# SAMD21.net
KiCad netlist of a schematic drawn in EAGLE
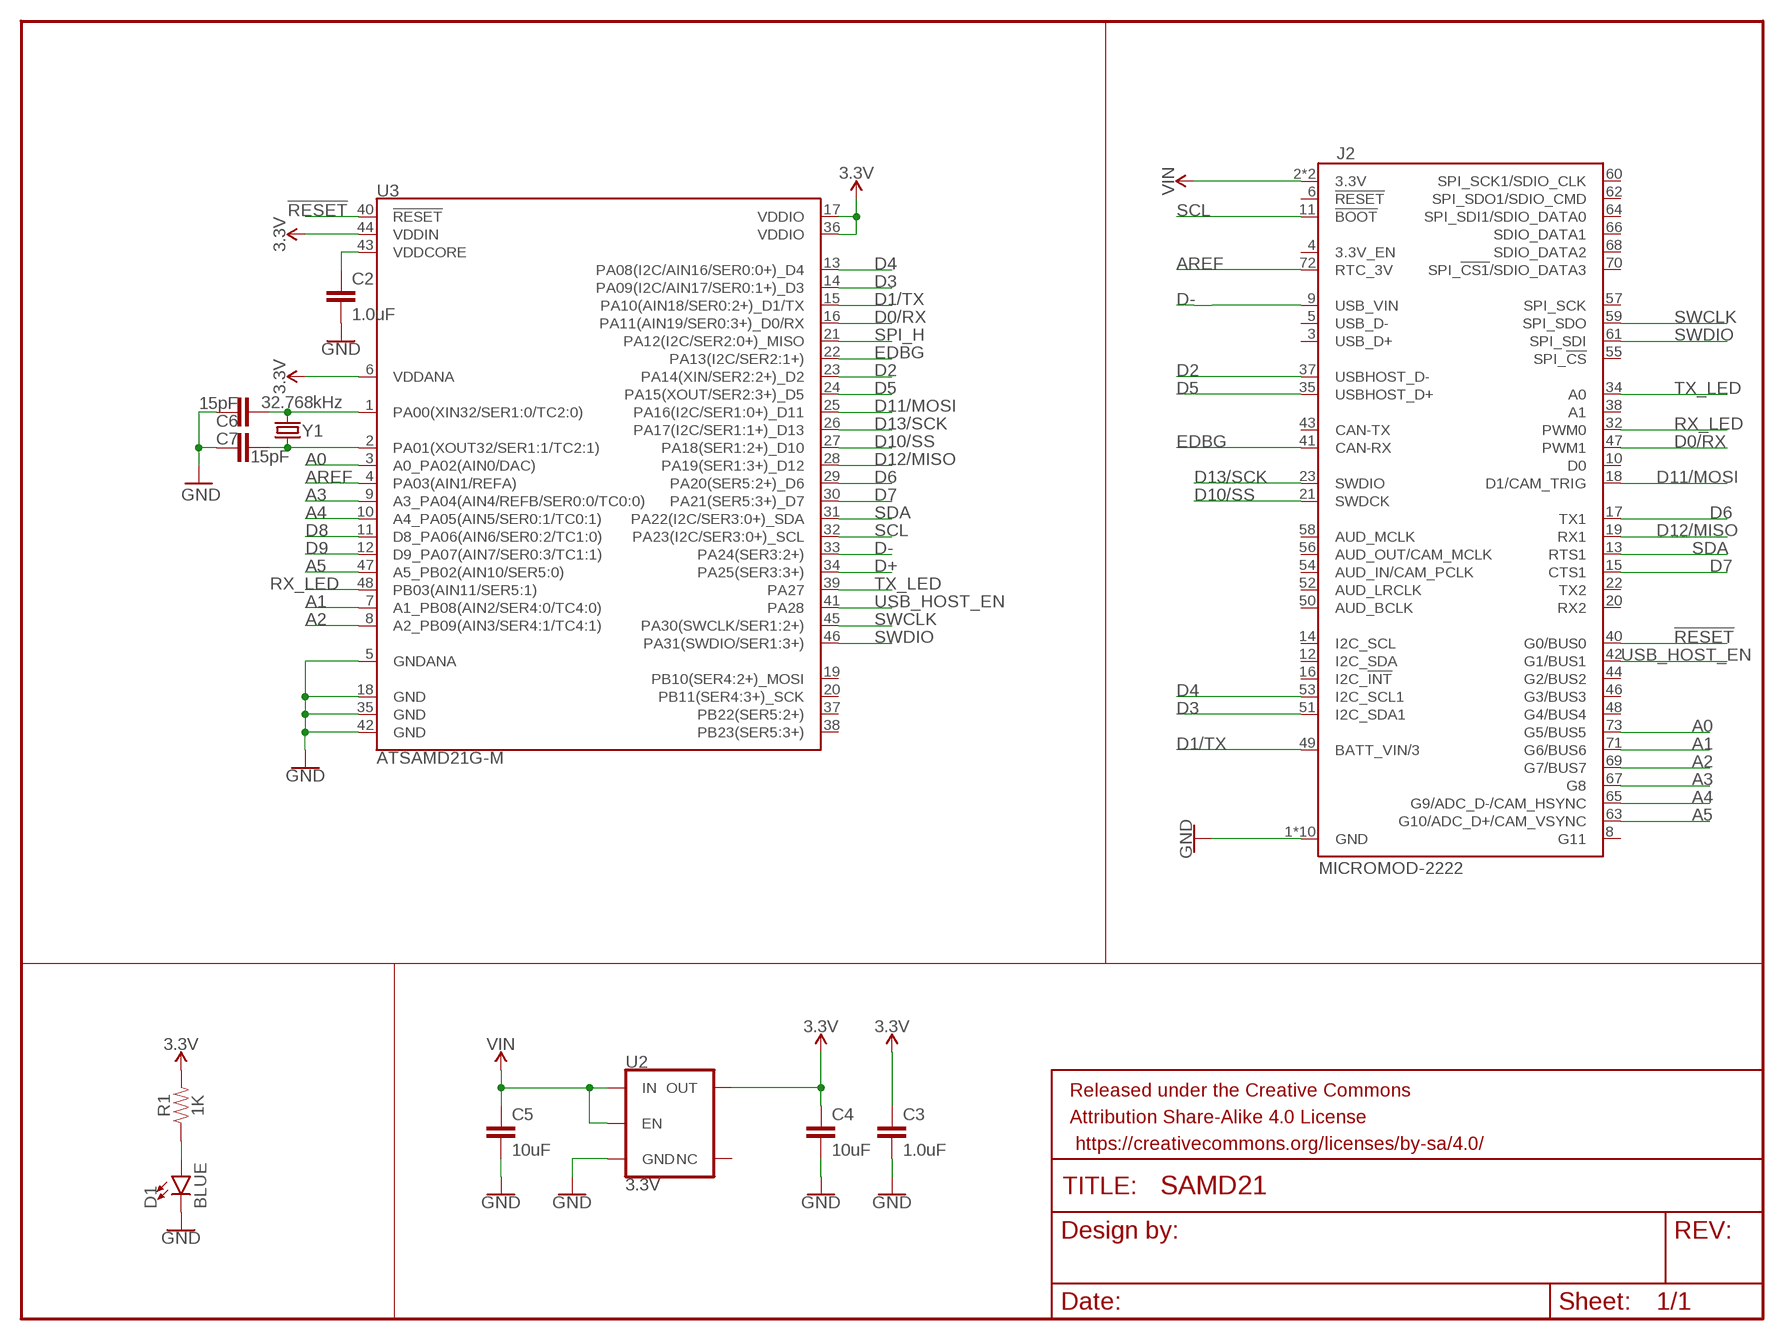
[diagram p0: schematic, sheet 1]

(export (version "E")
  (design (tool "Eeschema 10.0.6"))
  (components
    (comp (ref "C2")
      (value "1.0uF")
      (footprint "eagle-import:0603")
      (libsource (lib "eagle-import") (part "1.0UF-0603-16V-10%-X7R"))
    )
    (comp (ref "C3")
      (value "1.0uF")
      (footprint "eagle-import:0603")
      (libsource (lib "eagle-import") (part "1.0UF-0603-16V-10%-X7R"))
    )
    (comp (ref "C4")
      (value "10uF")
      (footprint "eagle-import:0603")
      (libsource (lib "eagle-import") (part "10UF-0603-6.3V-20%"))
    )
    (comp (ref "C5")
      (value "10uF")
      (footprint "eagle-import:0603")
      (libsource (lib "eagle-import") (part "10UF-0603-6.3V-20%"))
    )
    (comp (ref "C6")
      (value "15pF")
      (footprint "eagle-import:0402-CAP")
      (libsource (lib "eagle-import") (part "15PF-50V(+-5%)(0402)"))
    )
    (comp (ref "C7")
      (value "15pF")
      (footprint "eagle-import:0402-CAP")
      (libsource (lib "eagle-import") (part "15PF-50V(+-5%)(0402)"))
    )
    (comp (ref "D1")
      (value "BLUE")
      (footprint "eagle-import:LED-0603")
      (libsource (lib "eagle-import") (part "LED-BLUE0603"))
    )
    (comp (ref "FRAME1")
      (value "FRAME-LETTER")
      (footprint "eagle-import:CREATIVE_COMMONS")
      (libsource (lib "eagle-import") (part "FRAME-LETTER"))
    )
    (comp (ref "J2")
      (value "MICROMOD-2222")
      (footprint "eagle-import:M.2-CARD-E-22")
      (libsource (lib "eagle-import") (part "MICROMOD-2222"))
    )
    (comp (ref "R1")
      (value "1K")
      (footprint "eagle-import:0603")
      (libsource (lib "eagle-import") (part "0.05OHM-0603-1/5W-1%"))
    )
    (comp (ref "U2")
      (value "3.3V")
      (footprint "eagle-import:SOT23-5")
      (libsource (lib "eagle-import") (part "V_REG_AP2112K-3.3V"))
    )
    (comp (ref "U3")
      (value "ATSAMD21G-M")
      (footprint "eagle-import:QFN-48")
      (libsource (lib "eagle-import") (part "ATSAMD21G-M"))
    )
    (comp (ref "Y1")
      (value "32.768kHz")
      (footprint "eagle-import:CRYSTAL-SMD-3.2X1.5MM")
      (libsource (lib "eagle-import") (part "CRYSTAL3.2X1.5MM"))
    )
  )
  (nets
    (net (code "1") (name "/A0") (class "Default")
      (node (ref "J2") (pin "73") (pinfunction "G5/BUS5_73") (pintype "bidirectional"))
      (node (ref "U3") (pin "3") (pinfunction "A0_PA02(AIN0/DAC)_3") (pintype "bidirectional"))
    )
    (net (code "2") (name "/A1") (class "Default")
      (node (ref "J2") (pin "71") (pinfunction "G6/BUS6_71") (pintype "bidirectional"))
      (node (ref "U3") (pin "7") (pinfunction "A1_PB08(AIN2/SER4:0/TC4:0)_7") (pintype "bidirectional"))
    )
    (net (code "3") (name "/A2") (class "Default")
      (node (ref "J2") (pin "69") (pinfunction "G7/BUS7_69") (pintype "bidirectional"))
      (node (ref "U3") (pin "8") (pinfunction "A2_PB09(AIN3/SER4:1/TC4:1)_8") (pintype "bidirectional"))
    )
    (net (code "4") (name "/A3") (class "Default")
      (node (ref "J2") (pin "67") (pinfunction "G8_67") (pintype "bidirectional"))
      (node (ref "U3") (pin "9") (pinfunction "A3_PA04(AIN4/REFB/SER0:0/TC0:0)_9") (pintype "bidirectional"))
    )
    (net (code "5") (name "/A4") (class "Default")
      (node (ref "J2") (pin "65") (pinfunction "G9/ADC_D-/CAM_HSYNC_65") (pintype "bidirectional"))
      (node (ref "U3") (pin "10") (pinfunction "A4_PA05(AIN5/SER0:1/TC0:1)_10") (pintype "bidirectional"))
    )
    (net (code "6") (name "/A5") (class "Default")
      (node (ref "J2") (pin "63") (pinfunction "G10/ADC_D+/CAM_VSYNC_63") (pintype "bidirectional"))
      (node (ref "U3") (pin "47") (pinfunction "A5_PB02(AIN10/SER5:0)_47") (pintype "bidirectional"))
    )
    (net (code "7") (name "/AREF") (class "Default")
      (node (ref "J2") (pin "72") (pinfunction "RTC_3V_72") (pintype "bidirectional"))
      (node (ref "U3") (pin "4") (pinfunction "PA03(AIN1/REFA)_4") (pintype "bidirectional"))
    )
    (net (code "8") (name "/D+") (class "Default")
      (node (ref "U3") (pin "34") (pinfunction "PA25(SER3:3+)_34") (pintype "bidirectional"))
    )
    (net (code "9") (name "/D-") (class "Default")
      (node (ref "J2") (pin "9") (pinfunction "USB_VIN_9") (pintype "bidirectional"))
      (node (ref "U3") (pin "33") (pinfunction "PA24(SER3:2+)_33") (pintype "bidirectional"))
    )
    (net (code "10") (name "/D0{slash}RX") (class "Default")
      (node (ref "J2") (pin "47") (pinfunction "PWM1_47") (pintype "bidirectional"))
      (node (ref "U3") (pin "16") (pinfunction "PA11(AIN19/SER0:3+)_D0/RX_16") (pintype "bidirectional"))
    )
    (net (code "11") (name "/D1{slash}TX") (class "Default")
      (node (ref "J2") (pin "49") (pinfunction "BATT_VIN/3_49") (pintype "bidirectional"))
      (node (ref "U3") (pin "15") (pinfunction "PA10(AIN18/SER0:2+)_D1/TX_15") (pintype "bidirectional"))
    )
    (net (code "12") (name "/D2") (class "Default")
      (node (ref "J2") (pin "37") (pinfunction "USBHOST_D-_37") (pintype "bidirectional"))
      (node (ref "U3") (pin "23") (pinfunction "PA14(XIN/SER2:2+)_D2_23") (pintype "bidirectional"))
    )
    (net (code "13") (name "/D3") (class "Default")
      (node (ref "J2") (pin "51") (pinfunction "I2C_SDA1_51") (pintype "bidirectional"))
      (node (ref "U3") (pin "14") (pinfunction "PA09(I2C/AIN17/SER0:1+)_D3_14") (pintype "bidirectional"))
    )
    (net (code "14") (name "/D4") (class "Default")
      (node (ref "J2") (pin "53") (pinfunction "I2C_SCL1_53") (pintype "bidirectional"))
      (node (ref "U3") (pin "13") (pinfunction "PA08(I2C/AIN16/SER0:0+)_D4_13") (pintype "bidirectional"))
    )
    (net (code "15") (name "/D5") (class "Default")
      (node (ref "J2") (pin "35") (pinfunction "USBHOST_D+_35") (pintype "bidirectional"))
      (node (ref "U3") (pin "24") (pinfunction "PA15(XOUT/SER2:3+)_D5_24") (pintype "bidirectional"))
    )
    (net (code "16") (name "/D6") (class "Default")
      (node (ref "J2") (pin "17") (pinfunction "TX1_17") (pintype "bidirectional"))
      (node (ref "U3") (pin "29") (pinfunction "PA20(SER5:2+)_D6_29") (pintype "bidirectional"))
    )
    (net (code "17") (name "/D7") (class "Default")
      (node (ref "J2") (pin "15") (pinfunction "CTS1_15") (pintype "bidirectional"))
      (node (ref "U3") (pin "30") (pinfunction "PA21(SER5:3+)_D7_30") (pintype "bidirectional"))
    )
    (net (code "18") (name "/D8") (class "Default")
      (node (ref "U3") (pin "11") (pinfunction "D8_PA06(AIN6/SER0:2/TC1:0)_11") (pintype "bidirectional"))
    )
    (net (code "19") (name "/D9") (class "Default")
      (node (ref "U3") (pin "12") (pinfunction "D9_PA07(AIN7/SER0:3/TC1:1)_12") (pintype "bidirectional"))
    )
    (net (code "20") (name "/D10{slash}SS") (class "Default")
      (node (ref "J2") (pin "21") (pinfunction "SWDCK_21") (pintype "bidirectional"))
      (node (ref "U3") (pin "27") (pinfunction "PA18(SER1:2+)_D10_27") (pintype "bidirectional"))
    )
    (net (code "21") (name "/D11{slash}MOSI") (class "Default")
      (node (ref "J2") (pin "18") (pinfunction "D1/CAM_TRIG_18") (pintype "bidirectional"))
      (node (ref "U3") (pin "25") (pinfunction "PA16(I2C/SER1:0+)_D11_25") (pintype "bidirectional"))
    )
    (net (code "22") (name "/D12{slash}MISO") (class "Default")
      (node (ref "J2") (pin "19") (pinfunction "RX1_19") (pintype "bidirectional"))
      (node (ref "U3") (pin "28") (pinfunction "PA19(SER1:3+)_D12_28") (pintype "bidirectional"))
    )
    (net (code "23") (name "/D13{slash}SCK") (class "Default")
      (node (ref "J2") (pin "23") (pinfunction "SWDIO_23") (pintype "bidirectional"))
      (node (ref "U3") (pin "26") (pinfunction "PA17(I2C/SER1:1+)_D13_26") (pintype "bidirectional"))
    )
    (net (code "24") (name "/EDBG") (class "Default")
      (node (ref "J2") (pin "41") (pinfunction "CAN-RX_41") (pintype "bidirectional"))
      (node (ref "U3") (pin "22") (pinfunction "PA13(I2C/SER2:1+)_22") (pintype "bidirectional"))
    )
    (net (code "25") (name "/RX_LED") (class "Default")
      (node (ref "J2") (pin "32") (pinfunction "PWM0_32") (pintype "bidirectional"))
      (node (ref "U3") (pin "48") (pinfunction "PB03(AIN11/SER5:1)_48") (pintype "bidirectional"))
    )
    (net (code "26") (name "/SCL") (class "Default")
      (node (ref "J2") (pin "11") (pinfunction "~{BOOT}_11") (pintype "bidirectional"))
      (node (ref "U3") (pin "32") (pinfunction "PA23(I2C/SER3:0+)_SCL_32") (pintype "bidirectional"))
    )
    (net (code "27") (name "/SDA") (class "Default")
      (node (ref "J2") (pin "13") (pinfunction "RTS1_13") (pintype "bidirectional"))
      (node (ref "U3") (pin "31") (pinfunction "PA22(I2C/SER3:0+)_SDA_31") (pintype "bidirectional"))
    )
    (net (code "28") (name "/SPI_H") (class "Default")
      (node (ref "U3") (pin "21") (pinfunction "PA12(I2C/SER2:0+)_MISO_21") (pintype "bidirectional"))
    )
    (net (code "29") (name "/SWCLK") (class "Default")
      (node (ref "J2") (pin "59") (pinfunction "SPI_SDO_59") (pintype "bidirectional"))
      (node (ref "U3") (pin "45") (pinfunction "PA30(SWCLK/SER1:2+)_45") (pintype "bidirectional"))
    )
    (net (code "30") (name "/SWDIO") (class "Default")
      (node (ref "J2") (pin "61") (pinfunction "SPI_SDI_61") (pintype "bidirectional"))
      (node (ref "U3") (pin "46") (pinfunction "PA31(SWDIO/SER1:3+)_46") (pintype "bidirectional"))
    )
    (net (code "31") (name "/TX_LED") (class "Default")
      (node (ref "J2") (pin "34") (pinfunction "A0_34") (pintype "bidirectional"))
      (node (ref "U3") (pin "39") (pinfunction "PA27_39") (pintype "bidirectional"))
    )
    (net (code "32") (name "/USB_HOST_EN") (class "Default")
      (node (ref "J2") (pin "42") (pinfunction "G1/BUS1_42") (pintype "bidirectional"))
      (node (ref "U3") (pin "41") (pinfunction "PA28_41") (pintype "bidirectional"))
    )
    (net (code "33") (name "/~{RESET}") (class "Default")
      (node (ref "J2") (pin "40") (pinfunction "G0/BUS0_40") (pintype "bidirectional"))
      (node (ref "U3") (pin "40") (pinfunction "~{RESET}_40") (pintype "bidirectional"))
    )
    (net (code "34") (name "3.3V") (class "Default")
      (node (ref "C3") (pin "1") (pinfunction "1_1") (pintype "passive"))
      (node (ref "C4") (pin "1") (pinfunction "1_1") (pintype "passive"))
      (node (ref "R1") (pin "2") (pinfunction "2_2") (pintype "passive"))
      (node (ref "U2") (pin "5") (pinfunction "OUT_5") (pintype "passive"))
      (node (ref "U3") (pin "17") (pinfunction "VDDIO_17") (pintype "bidirectional"))
      (node (ref "U3") (pin "36") (pinfunction "VDDIO_36") (pintype "bidirectional"))
      (node (ref "U3") (pin "44") (pinfunction "VDDIN_44") (pintype "bidirectional"))
      (node (ref "U3") (pin "6") (pinfunction "VDDANA_6") (pintype "bidirectional"))
    )
    (net (code "35") (name "GND") (class "Default")
      (node (ref "C2") (pin "2") (pinfunction "2_2") (pintype "passive"))
      (node (ref "C3") (pin "2") (pinfunction "2_2") (pintype "passive"))
      (node (ref "C4") (pin "2") (pinfunction "2_2") (pintype "passive"))
      (node (ref "C5") (pin "2") (pinfunction "2_2") (pintype "passive"))
      (node (ref "C6") (pin "1") (pinfunction "1_1") (pintype "passive"))
      (node (ref "C7") (pin "2") (pinfunction "2_2") (pintype "passive"))
      (node (ref "D1") (pin "C") (pinfunction "C_C") (pintype "passive"))
      (node (ref "J2") (pin "1") (pinfunction "GND_1") (pintype "bidirectional"))
      (node (ref "J2") (pin "33") (pinfunction "GND_33") (pintype "bidirectional"))
      (node (ref "J2") (pin "36") (pinfunction "GND_36") (pintype "bidirectional"))
      (node (ref "J2") (pin "39") (pinfunction "GND_39") (pintype "bidirectional"))
      (node (ref "J2") (pin "45") (pinfunction "GND_45") (pintype "bidirectional"))
      (node (ref "J2") (pin "7") (pinfunction "GND_7") (pintype "bidirectional"))
      (node (ref "J2") (pin "75") (pinfunction "GND_75") (pintype "bidirectional"))
      (node (ref "J2") (pin "GND1") (pinfunction "GND_GND1") (pintype "bidirectional"))
      (node (ref "J2") (pin "GND2") (pinfunction "GND_GND2") (pintype "bidirectional"))
      (node (ref "J2") (pin "GND3") (pinfunction "GND_GND3") (pintype "bidirectional"))
      (node (ref "U2") (pin "2") (pinfunction "GND_2") (pintype "input"))
      (node (ref "U3") (pin "18") (pinfunction "GND_18") (pintype "bidirectional"))
      (node (ref "U3") (pin "35") (pinfunction "GND_35") (pintype "bidirectional"))
      (node (ref "U3") (pin "42") (pinfunction "GND_42") (pintype "bidirectional"))
      (node (ref "U3") (pin "5") (pinfunction "GNDANA_5") (pintype "bidirectional"))
    )
    (net (code "36") (name "Net-(D1-PadA)") (class "Default")
      (node (ref "D1") (pin "A") (pinfunction "A_A") (pintype "passive"))
      (node (ref "R1") (pin "1") (pinfunction "1_1") (pintype "passive"))
    )
    (net (code "37") (name "Net-(U3-PA00(XIN32{slash}SER1:0{slash}TC2:0))") (class "Default")
      (node (ref "C6") (pin "2") (pinfunction "2_2") (pintype "passive"))
      (node (ref "U3") (pin "1") (pinfunction "PA00(XIN32/SER1:0/TC2:0)_1") (pintype "bidirectional"))
      (node (ref "Y1") (pin "P$2") (pinfunction "2_P$2") (pintype "passive"))
    )
    (net (code "38") (name "Net-(U3-PA01(XOUT32{slash}SER1:1{slash}TC2:1))") (class "Default")
      (node (ref "C7") (pin "1") (pinfunction "1_1") (pintype "passive"))
      (node (ref "U3") (pin "2") (pinfunction "PA01(XOUT32/SER1:1/TC2:1)_2") (pintype "bidirectional"))
      (node (ref "Y1") (pin "P$1") (pinfunction "1_P$1") (pintype "passive"))
    )
    (net (code "39") (name "Net-(U3-VDDCORE)") (class "Default")
      (node (ref "C2") (pin "1") (pinfunction "1_1") (pintype "passive"))
      (node (ref "U3") (pin "43") (pinfunction "VDDCORE_43") (pintype "bidirectional"))
    )
    (net (code "40") (name "VIN") (class "Default")
      (node (ref "C5") (pin "1") (pinfunction "1_1") (pintype "passive"))
      (node (ref "J2") (pin "2") (pinfunction "3.3V_2") (pintype "bidirectional"))
      (node (ref "J2") (pin "74") (pinfunction "3.3V_74") (pintype "bidirectional"))
      (node (ref "U2") (pin "1") (pinfunction "IN_1") (pintype "input"))
      (node (ref "U2") (pin "3") (pinfunction "EN_3") (pintype "input"))
    )
    (net (code "41") (name "unconnected-(J2-3.3V_EN-Pad4)") (class "Default")
      (node (ref "J2") (pin "4") (pinfunction "3.3V_EN_4") (pintype "bidirectional"))
    )
    (net (code "42") (name "unconnected-(J2-A1-Pad38)") (class "Default")
      (node (ref "J2") (pin "38") (pinfunction "A1_38") (pintype "bidirectional"))
    )
    (net (code "43") (name "unconnected-(J2-AUD_BCLK-Pad50)") (class "Default")
      (node (ref "J2") (pin "50") (pinfunction "AUD_BCLK_50") (pintype "bidirectional"))
    )
    (net (code "44") (name "unconnected-(J2-AUD_IN{slash}CAM_PCLK-Pad54)") (class "Default")
      (node (ref "J2") (pin "54") (pinfunction "AUD_IN/CAM_PCLK_54") (pintype "bidirectional"))
    )
    (net (code "45") (name "unconnected-(J2-AUD_LRCLK-Pad52)") (class "Default")
      (node (ref "J2") (pin "52") (pinfunction "AUD_LRCLK_52") (pintype "bidirectional"))
    )
    (net (code "46") (name "unconnected-(J2-AUD_MCLK-Pad58)") (class "Default")
      (node (ref "J2") (pin "58") (pinfunction "AUD_MCLK_58") (pintype "bidirectional"))
    )
    (net (code "47") (name "unconnected-(J2-AUD_OUT{slash}CAM_MCLK-Pad56)") (class "Default")
      (node (ref "J2") (pin "56") (pinfunction "AUD_OUT/CAM_MCLK_56") (pintype "bidirectional"))
    )
    (net (code "48") (name "unconnected-(J2-CAN-TX-Pad43)") (class "Default")
      (node (ref "J2") (pin "43") (pinfunction "CAN-TX_43") (pintype "bidirectional"))
    )
    (net (code "49") (name "unconnected-(J2-D0-Pad10)") (class "Default")
      (node (ref "J2") (pin "10") (pinfunction "D0_10") (pintype "bidirectional"))
    )
    (net (code "50") (name "unconnected-(J2-G2{slash}BUS2-Pad44)") (class "Default")
      (node (ref "J2") (pin "44") (pinfunction "G2/BUS2_44") (pintype "bidirectional"))
    )
    (net (code "51") (name "unconnected-(J2-G3{slash}BUS3-Pad46)") (class "Default")
      (node (ref "J2") (pin "46") (pinfunction "G3/BUS3_46") (pintype "bidirectional"))
    )
    (net (code "52") (name "unconnected-(J2-G4{slash}BUS4-Pad48)") (class "Default")
      (node (ref "J2") (pin "48") (pinfunction "G4/BUS4_48") (pintype "bidirectional"))
    )
    (net (code "53") (name "unconnected-(J2-G11-Pad8)") (class "Default")
      (node (ref "J2") (pin "8") (pinfunction "G11_8") (pintype "bidirectional"))
    )
    (net (code "54") (name "unconnected-(J2-I2C_SCL-Pad14)") (class "Default")
      (node (ref "J2") (pin "14") (pinfunction "I2C_SCL_14") (pintype "bidirectional"))
    )
    (net (code "55") (name "unconnected-(J2-I2C_SDA-Pad12)") (class "Default")
      (node (ref "J2") (pin "12") (pinfunction "I2C_SDA_12") (pintype "bidirectional"))
    )
    (net (code "56") (name "unconnected-(J2-I2C_~{INT}-Pad16)") (class "Default")
      (node (ref "J2") (pin "16") (pinfunction "I2C_~{INT}_16") (pintype "bidirectional"))
    )
    (net (code "57") (name "unconnected-(J2-RX2-Pad20)") (class "Default")
      (node (ref "J2") (pin "20") (pinfunction "RX2_20") (pintype "bidirectional"))
    )
    (net (code "58") (name "unconnected-(J2-SDIO_DATA1-Pad66)") (class "Default")
      (node (ref "J2") (pin "66") (pinfunction "SDIO_DATA1_66") (pintype "bidirectional"))
    )
    (net (code "59") (name "unconnected-(J2-SDIO_DATA2-Pad68)") (class "Default")
      (node (ref "J2") (pin "68") (pinfunction "SDIO_DATA2_68") (pintype "bidirectional"))
    )
    (net (code "60") (name "unconnected-(J2-SPI_SCK-Pad57)") (class "Default")
      (node (ref "J2") (pin "57") (pinfunction "SPI_SCK_57") (pintype "bidirectional"))
    )
    (net (code "61") (name "unconnected-(J2-SPI_SCK1{slash}SDIO_CLK-Pad60)") (class "Default")
      (node (ref "J2") (pin "60") (pinfunction "SPI_SCK1/SDIO_CLK_60") (pintype "bidirectional"))
    )
    (net (code "62") (name "unconnected-(J2-SPI_SDI1{slash}SDIO_DATA0-Pad64)") (class "Default")
      (node (ref "J2") (pin "64") (pinfunction "SPI_SDI1/SDIO_DATA0_64") (pintype "bidirectional"))
    )
    (net (code "63") (name "unconnected-(J2-SPI_SDO1{slash}SDIO_CMD-Pad62)") (class "Default")
      (node (ref "J2") (pin "62") (pinfunction "SPI_SDO1/SDIO_CMD_62") (pintype "bidirectional"))
    )
    (net (code "64") (name "unconnected-(J2-SPI_~{CS1}{slash}SDIO_DATA3-Pad70)") (class "Default")
      (node (ref "J2") (pin "70") (pinfunction "SPI_~{CS1}/SDIO_DATA3_70") (pintype "bidirectional"))
    )
    (net (code "65") (name "unconnected-(J2-SPI_~{CS}-Pad55)") (class "Default")
      (node (ref "J2") (pin "55") (pinfunction "SPI_~{CS}_55") (pintype "bidirectional"))
    )
    (net (code "66") (name "unconnected-(J2-TX2-Pad22)") (class "Default")
      (node (ref "J2") (pin "22") (pinfunction "TX2_22") (pintype "bidirectional"))
    )
    (net (code "67") (name "unconnected-(J2-USB_D+-Pad3)") (class "Default")
      (node (ref "J2") (pin "3") (pinfunction "USB_D+_3") (pintype "bidirectional"))
    )
    (net (code "68") (name "unconnected-(J2-USB_D--Pad5)") (class "Default")
      (node (ref "J2") (pin "5") (pinfunction "USB_D-_5") (pintype "bidirectional"))
    )
    (net (code "69") (name "unconnected-(J2-~{RESET}-Pad6)") (class "Default")
      (node (ref "J2") (pin "6") (pinfunction "~{RESET}_6") (pintype "bidirectional"))
    )
    (net (code "70") (name "unconnected-(U2-NC-Pad4)") (class "Default")
      (node (ref "U2") (pin "4") (pinfunction "NC_4") (pintype "no_connect"))
    )
    (net (code "71") (name "unconnected-(U3-PB10(SER4:2+)_MOSI-Pad19)") (class "Default")
      (node (ref "U3") (pin "19") (pinfunction "PB10(SER4:2+)_MOSI_19") (pintype "bidirectional"))
    )
    (net (code "72") (name "unconnected-(U3-PB11(SER4:3+)_SCK-Pad20)") (class "Default")
      (node (ref "U3") (pin "20") (pinfunction "PB11(SER4:3+)_SCK_20") (pintype "bidirectional"))
    )
    (net (code "73") (name "unconnected-(U3-PB22(SER5:2+)-Pad37)") (class "Default")
      (node (ref "U3") (pin "37") (pinfunction "PB22(SER5:2+)_37") (pintype "bidirectional"))
    )
    (net (code "74") (name "unconnected-(U3-PB23(SER5:3+)-Pad38)") (class "Default")
      (node (ref "U3") (pin "38") (pinfunction "PB23(SER5:3+)_38") (pintype "bidirectional"))
    )
  )
)
